# RF_AMP.net
KiCad netlist of a schematic drawn in Altium Designer
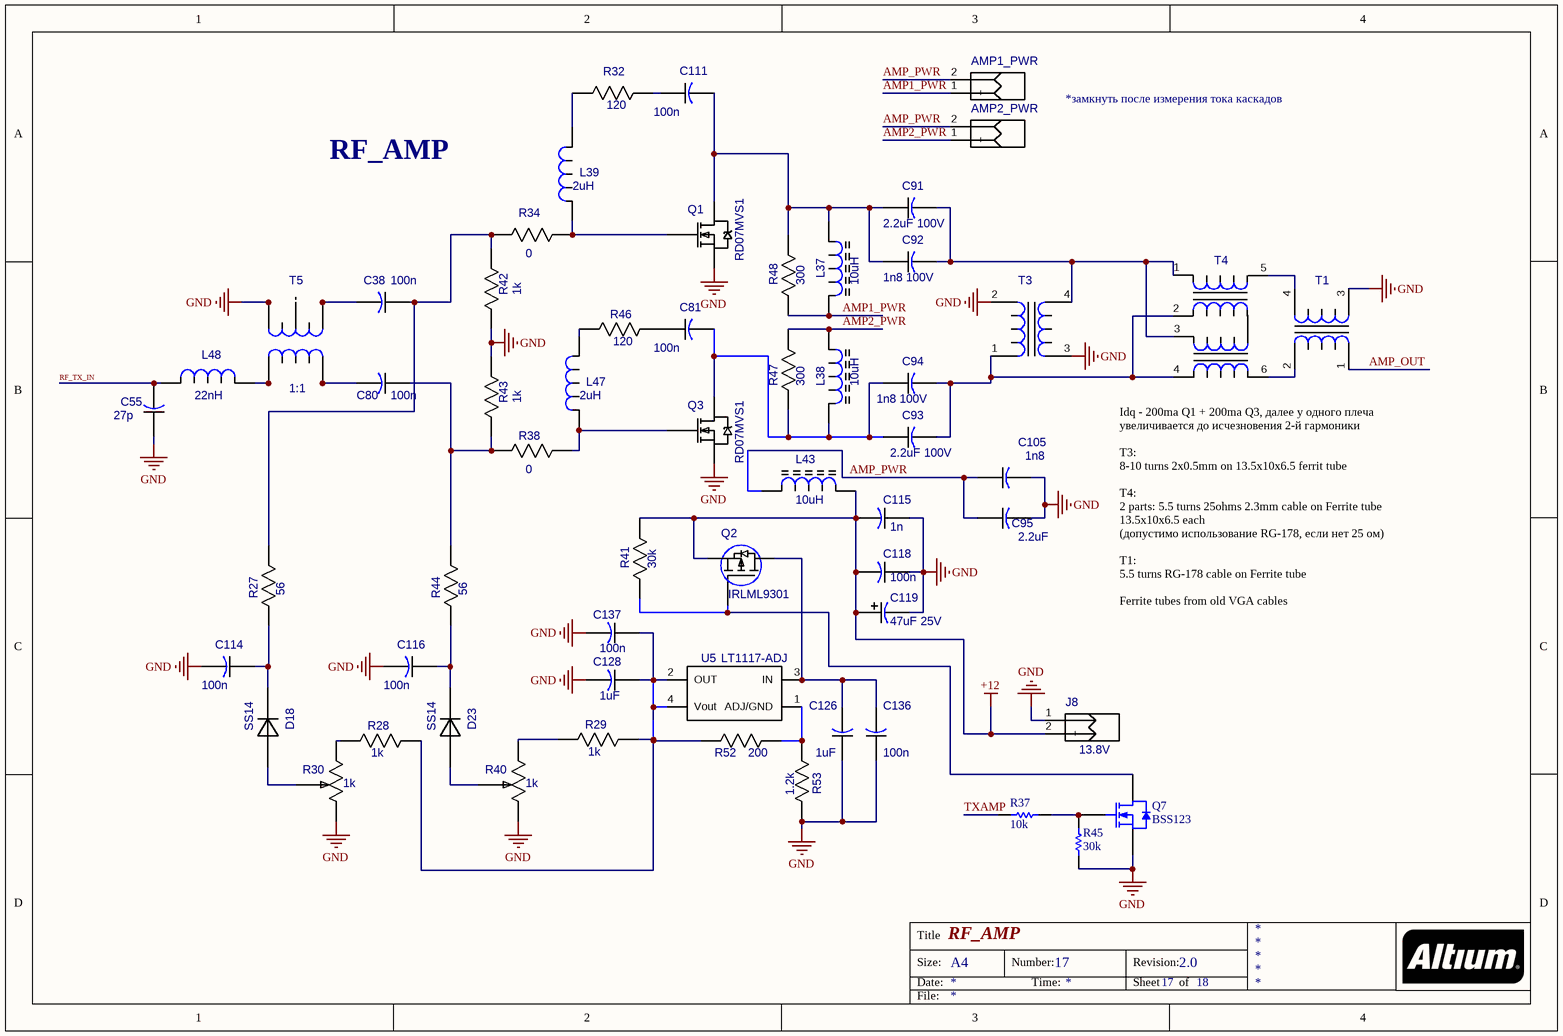
[diagram p0: RF_AMP.SchDoc]

(export (version "E")
  (design (tool "Eeschema 10.0.6"))
  (components
    (comp (ref "AMP1_PWR")
      (value "51022-0200")
      (footprint "51022-0200")
      (libsource (lib "*") (part "51022-0200"))
    )
    (comp (ref "AMP2_PWR")
      (value "51022-0200")
      (footprint "51022-0200")
      (libsource (lib "*") (part "51022-0200"))
    )
    (comp (ref "C38")
      (value "100n")
      (footprint "CAP_0805")
      (description "CAP_0805")
      (libsource (lib "*") (part "CAP_0805"))
    )
    (comp (ref "C55")
      (value "27p")
      (footprint "CAP_0805")
      (description "CAP_0805")
      (libsource (lib "*") (part "CAP_0805"))
    )
    (comp (ref "C80")
      (value "100n")
      (footprint "CAP_0805")
      (description "CAP_0805")
      (libsource (lib "*") (part "CAP_0805"))
    )
    (comp (ref "C81")
      (value "100n")
      (footprint "CAP_1206")
      (description "CAP_1206")
      (libsource (lib "*") (part "CAP_1206"))
    )
    (comp (ref "C91")
      (value "2.2uF 100V")
      (footprint "CAP_1206")
      (description "CAP_1206")
      (libsource (lib "*") (part "CAP_1206"))
    )
    (comp (ref "C92")
      (value "1n8 100V")
      (footprint "CAP_1206")
      (description "CAP_1206")
      (libsource (lib "*") (part "CAP_1206"))
    )
    (comp (ref "C93")
      (value "2.2uF 100V")
      (footprint "CAP_1206")
      (description "CAP_1206")
      (libsource (lib "*") (part "CAP_1206"))
    )
    (comp (ref "C94")
      (value "1n8 100V")
      (footprint "CAP_1206")
      (description "CAP_1206")
      (libsource (lib "*") (part "CAP_1206"))
    )
    (comp (ref "C95")
      (value "2.2uF")
      (footprint "CAP_1206")
      (description "CAP_1206")
      (libsource (lib "*") (part "CAP_1206"))
    )
    (comp (ref "C105")
      (value "1n8")
      (footprint "CAP_1206")
      (description "CAP_1206")
      (libsource (lib "*") (part "CAP_1206"))
    )
    (comp (ref "C111")
      (value "100n")
      (footprint "CAP_1206")
      (description "CAP_1206")
      (libsource (lib "*") (part "CAP_1206"))
    )
    (comp (ref "C114")
      (value "100n")
      (footprint "CAP_0805")
      (description "CAP_0805")
      (libsource (lib "*") (part "CAP_0805"))
    )
    (comp (ref "C115")
      (value "1n")
      (footprint "CAP_0805")
      (description "CAP_0805")
      (libsource (lib "*") (part "CAP_0805"))
    )
    (comp (ref "C116")
      (value "100n")
      (footprint "CAP_0805")
      (description "CAP_0805")
      (libsource (lib "*") (part "CAP_0805"))
    )
    (comp (ref "C118")
      (value "100n")
      (footprint "CAP_0805")
      (description "CAP_0805")
      (libsource (lib "*") (part "CAP_0805"))
    )
    (comp (ref "C119")
      (value "47uF 25V")
      (footprint "CAPAE_6.6x6.6h5.4")
      (description "CAPAE_6.6x6.6h5.4")
      (libsource (lib "*") (part "CAPAE_6.6x6.6h5.4"))
    )
    (comp (ref "C126")
      (value "1uF")
      (footprint "CAP_0805")
      (description "CAP_0805")
      (libsource (lib "*") (part "CAP_0805"))
    )
    (comp (ref "C128")
      (value "1uF")
      (footprint "CAP_0805")
      (description "CAP_0805")
      (libsource (lib "*") (part "CAP_0805"))
    )
    (comp (ref "C136")
      (value "100n")
      (footprint "CAP_0805")
      (description "CAP_0805")
      (libsource (lib "*") (part "CAP_0805"))
    )
    (comp (ref "C137")
      (value "100n")
      (footprint "CAP_0805")
      (description "CAP_0805")
      (libsource (lib "*") (part "CAP_0805"))
    )
    (comp (ref "D18") (value "SS14") (footprint "SS14") (libsource (lib "*") (part "SS14")))
    (comp (ref "D23") (value "SS14") (footprint "SS14") (libsource (lib "*") (part "SS14")))
    (comp (ref "J8")
      (value "13.8V")
      (footprint "1986717-2")
      (description "JX2")
      (libsource (lib "*") (part "1986717-2"))
    )
    (comp (ref "L37")
      (value "10uH")
      (footprint "IND_FERRITE_CORE")
      (description "Inductor")
      (libsource (lib "*") (part "IND_FERRITE_CORE"))
    )
    (comp (ref "L38")
      (value "10uH")
      (footprint "IND_FERRITE_CORE")
      (description "Inductor")
      (libsource (lib "*") (part "IND_FERRITE_CORE"))
    )
    (comp (ref "L39")
      (value "2uH")
      (footprint "IND_0805")
      (description "IND_0805")
      (libsource (lib "*") (part "IND_0805"))
    )
    (comp (ref "L43")
      (value "10uH")
      (footprint "IND_FERRITE_CORE")
      (description "Inductor")
      (libsource (lib "*") (part "IND_FERRITE_CORE"))
    )
    (comp (ref "L47")
      (value "2uH")
      (footprint "IND_0805")
      (description "IND_0805")
      (libsource (lib "*") (part "IND_0805"))
    )
    (comp (ref "L48")
      (value "22nH")
      (footprint "IND_0805")
      (description "IND_0805")
      (libsource (lib "*") (part "IND_0805"))
    )
    (comp (ref "Q1") (value "RD07MVS1") (footprint "RD07MVS1") (libsource (lib "*") (part "RD07MVS1")))
    (comp (ref "Q2")
      (value "IRLML9301")
      (footprint "SOT23")
      (description "MOSFET")
      (libsource (lib "*") (part "MOSFET_ENH_PD"))
    )
    (comp (ref "Q3") (value "RD07MVS1") (footprint "RD07MVS1") (libsource (lib "*") (part "RD07MVS1")))
    (comp (ref "Q7")
      (value "BSS123")
      (footprint "FAIR-SOT23-3_V")
      (fields (field (name "MANUFACTURER") "Fairchild"))
      (libsource (lib "Altium Content Vault") (part "NEMOS-GSD-3"))
    )
    (comp (ref "R27")
      (value "56")
      (footprint "RES_0805")
      (description "RES_0805")
      (libsource (lib "*") (part "RES_0805"))
    )
    (comp (ref "R28")
      (value "1k")
      (footprint "RES_0805")
      (description "RES_0805")
      (libsource (lib "*") (part "RES_0805"))
    )
    (comp (ref "R29")
      (value "1k")
      (footprint "RES_0805")
      (description "RES_0805")
      (libsource (lib "*") (part "RES_0805"))
    )
    (comp (ref "R30")
      (value "1k")
      (footprint "306J")
      (description "306J")
      (fields (field (name "Comment") "ADJ-1k"))
      (libsource (lib "*") (part "306J"))
    )
    (comp (ref "R32")
      (value "120")
      (footprint "RES_0805")
      (description "RES_0805")
      (libsource (lib "*") (part "RES_0805"))
    )
    (comp (ref "R34")
      (value "0")
      (footprint "RES_1206")
      (description "RES_1206")
      (libsource (lib "*") (part "RES_1206"))
    )
    (comp (ref "R37")
      (value "10k")
      (footprint "RESC2013X60X40NL20T25")
      (description "RES_0805")
      (fields (field (name "MANUFACTURER") "Panasonic") (field (name "PART NUMBER") "ERA-6AEB303V"))
      (libsource (lib "Altium Content Vault") (part "RES"))
    )
    (comp (ref "R38")
      (value "0")
      (footprint "RES_1206")
      (description "RES_1206")
      (libsource (lib "*") (part "RES_1206"))
    )
    (comp (ref "R40")
      (value "1k")
      (footprint "306J")
      (description "306J")
      (fields (field (name "Comment") "ADJ-1k"))
      (libsource (lib "*") (part "306J"))
    )
    (comp (ref "R41")
      (value "30k")
      (footprint "RES_0805")
      (description "RES_0805")
      (libsource (lib "*") (part "RES_0805"))
    )
    (comp (ref "R42")
      (value "1k")
      (footprint "RES_0805")
      (description "RES_0805")
      (libsource (lib "*") (part "RES_0805"))
    )
    (comp (ref "R43")
      (value "1k")
      (footprint "RES_0805")
      (description "RES_0805")
      (libsource (lib "*") (part "RES_0805"))
    )
    (comp (ref "R44")
      (value "56")
      (footprint "RES_0805")
      (description "RES_0805")
      (libsource (lib "*") (part "RES_0805"))
    )
    (comp (ref "R45")
      (value "30k")
      (footprint "RESC2013X60X40NL20T25")
      (description "RES_0805")
      (fields (field (name "MANUFACTURER") "Panasonic") (field (name "PART NUMBER") "ERA-6AEB303V"))
      (libsource (lib "Altium Content Vault") (part "RES"))
    )
    (comp (ref "R46")
      (value "120")
      (footprint "RES_0805")
      (description "RES_0805")
      (libsource (lib "*") (part "RES_0805"))
    )
    (comp (ref "R47")
      (value "300")
      (footprint "RES_1206")
      (description "RES_1206")
      (libsource (lib "*") (part "RES_1206"))
    )
    (comp (ref "R48")
      (value "300")
      (footprint "RES_1206")
      (description "RES_1206")
      (libsource (lib "*") (part "RES_1206"))
    )
    (comp (ref "R52")
      (value "200")
      (footprint "RES_0805")
      (description "RES_0805")
      (libsource (lib "*") (part "RES_0805"))
    )
    (comp (ref "R53")
      (value "1.2k")
      (footprint "RES_0805")
      (description "RES_0805")
      (libsource (lib "*") (part "RES_0805"))
    )
    (comp (ref "T1")
      (value "8T M2000HM 10*6*5")
      (footprint "Rutrof 2")
      (description "Transformer")
      (libsource (lib "*") (part "TRANSF_ICORE"))
    )
    (comp (ref "T3")
      (value "8T M2000HM 10*6*5")
      (footprint "Rutrof")
      (description "Transformer")
      (libsource (lib "*") (part "TRANSF_ICORE"))
    )
    (comp (ref "T4")
      (value "TRANSF_OUT")
      (footprint "TRANSF_OUT")
      (libsource (lib "RF-UNIT") (part "TRANSF_OUT_2"))
    )
    (comp (ref "T5")
      (value "1:1")
      (footprint "TRANSF_ACORE2")
      (libsource (lib "RF-UNIT_1") (part "TRANSF_ACORE2"))
    )
    (comp (ref "U5")
      (value "LT1117-ADJ")
      (footprint "LT1117IST-ADJ")
      (description "LT1117IST-ADJ")
      (libsource (lib "*") (part "LT1117IST-ADJ"))
    )
  )
  (nets
    (net (code "1") (name "+12") (class "Default")
      (node (ref "C115") (pin "2") (pinfunction "2_2") (pintype "passive"))
      (node (ref "C118") (pin "2") (pinfunction "2_2") (pintype "passive"))
      (node (ref "C119") (pin "1") (pinfunction "PLUS_1") (pintype "passive"))
      (node (ref "J8") (pin "2") (pinfunction "+_2") (pintype "passive"))
      (node (ref "L43") (pin "2") (pinfunction "B_2") (pintype "passive"))
      (node (ref "Q2") (pin "2") (pinfunction "S_2") (pintype "passive"))
      (node (ref "R41") (pin "2") (pinfunction "2_2") (pintype "passive"))
    )
    (net (code "2") (name "/AMP1_PWR") (class "Default")
      (node (ref "AMP1_PWR") (pin "1") (pinfunction "+_1") (pintype "passive"))
      (node (ref "L37") (pin "2") (pinfunction "B_2") (pintype "passive"))
      (node (ref "R48") (pin "1") (pinfunction "1_1") (pintype "passive"))
    )
    (net (code "3") (name "/AMP2_PWR") (class "Default")
      (node (ref "AMP2_PWR") (pin "1") (pinfunction "+_1") (pintype "passive"))
      (node (ref "L38") (pin "1") (pinfunction "A_1") (pintype "passive"))
      (node (ref "R47") (pin "2") (pinfunction "2_2") (pintype "passive"))
    )
    (net (code "4") (name "/AMP_OUT") (class "Default")
      (node (ref "T1") (pin "1") (pinfunction "P1_1") (pintype "passive"))
    )
    (net (code "5") (name "/AMP_PWR") (class "Default")
      (node (ref "AMP1_PWR") (pin "2") (pinfunction "-_2") (pintype "passive"))
      (node (ref "AMP2_PWR") (pin "2") (pinfunction "-_2") (pintype "passive"))
      (node (ref "C105") (pin "1") (pinfunction "1_1") (pintype "passive"))
      (node (ref "C95") (pin "1") (pinfunction "1_1") (pintype "passive"))
      (node (ref "L43") (pin "1") (pinfunction "A_1") (pintype "passive"))
    )
    (net (code "6") (name "/RF_TX_IN") (class "Default")
      (node (ref "C55") (pin "2") (pinfunction "2_2") (pintype "passive"))
      (node (ref "L48") (pin "1") (pinfunction "1_1") (pintype "passive"))
    )
    (net (code "7") (name "/TXAMP") (class "Default")
      (node (ref "R37") (pin "2") (pinfunction "2_2") (pintype "passive"))
    )
    (net (code "8") (name "GND") (class "Default")
      (node (ref "C105") (pin "2") (pinfunction "2_2") (pintype "passive"))
      (node (ref "C114") (pin "2") (pinfunction "2_2") (pintype "passive"))
      (node (ref "C115") (pin "1") (pinfunction "1_1") (pintype "passive"))
      (node (ref "C116") (pin "2") (pinfunction "2_2") (pintype "passive"))
      (node (ref "C118") (pin "1") (pinfunction "1_1") (pintype "passive"))
      (node (ref "C119") (pin "2") (pinfunction "MINUS_2") (pintype "passive"))
      (node (ref "C126") (pin "1") (pinfunction "1_1") (pintype "passive"))
      (node (ref "C128") (pin "2") (pinfunction "2_2") (pintype "passive"))
      (node (ref "C136") (pin "1") (pinfunction "1_1") (pintype "passive"))
      (node (ref "C137") (pin "2") (pinfunction "2_2") (pintype "passive"))
      (node (ref "C55") (pin "1") (pinfunction "1_1") (pintype "passive"))
      (node (ref "C95") (pin "2") (pinfunction "2_2") (pintype "passive"))
      (node (ref "J8") (pin "1") (pinfunction "-_1") (pintype "passive"))
      (node (ref "Q1") (pin "2") (pinfunction "S_2") (pintype "passive"))
      (node (ref "Q3") (pin "2") (pinfunction "S_2") (pintype "passive"))
      (node (ref "Q7") (pin "2") (pinfunction "S_2") (pintype "passive"))
      (node (ref "R30") (pin "1") (pinfunction "CCW_1") (pintype "passive"))
      (node (ref "R40") (pin "1") (pinfunction "CCW_1") (pintype "passive"))
      (node (ref "R42") (pin "1") (pinfunction "1_1") (pintype "passive"))
      (node (ref "R43") (pin "2") (pinfunction "2_2") (pintype "passive"))
      (node (ref "R45") (pin "1") (pinfunction "1_1") (pintype "passive"))
      (node (ref "R53") (pin "2") (pinfunction "2_2") (pintype "passive"))
      (node (ref "T1") (pin "3") (pinfunction "S1_3") (pintype "passive"))
      (node (ref "T3") (pin "2") (pinfunction "P2_2") (pintype "passive"))
      (node (ref "T3") (pin "3") (pinfunction "S1_3") (pintype "passive"))
      (node (ref "T5") (pin "3") (pinfunction "S3_3") (pintype "passive"))
      (node (ref "T5") (pin "9") (pinfunction "0_9") (pintype "passive"))
    )
    (net (code "9") (name "Net-(C38-Pad1)") (class "Default")
      (node (ref "C38") (pin "1") (pinfunction "1_1") (pintype "passive"))
      (node (ref "R27") (pin "2") (pinfunction "2_2") (pintype "passive"))
      (node (ref "R34") (pin "1") (pinfunction "1_1") (pintype "passive"))
      (node (ref "R42") (pin "2") (pinfunction "2_2") (pintype "passive"))
    )
    (net (code "10") (name "Net-(C80-Pad1)") (class "Default")
      (node (ref "C80") (pin "1") (pinfunction "1_1") (pintype "passive"))
      (node (ref "R38") (pin "1") (pinfunction "1_1") (pintype "passive"))
      (node (ref "R43") (pin "1") (pinfunction "1_1") (pintype "passive"))
      (node (ref "R44") (pin "2") (pinfunction "2_2") (pintype "passive"))
    )
    (net (code "11") (name "Net-(C81-Pad1)") (class "Default")
      (node (ref "C81") (pin "1") (pinfunction "1_1") (pintype "passive"))
      (node (ref "R46") (pin "2") (pinfunction "2_2") (pintype "passive"))
    )
    (net (code "12") (name "Net-(C111-Pad1)") (class "Default")
      (node (ref "C111") (pin "1") (pinfunction "1_1") (pintype "passive"))
      (node (ref "R32") (pin "2") (pinfunction "2_2") (pintype "passive"))
    )
    (net (code "13") (name "Net-(D18-A)") (class "Default")
      (node (ref "D18") (pin "2") (pinfunction "A_2") (pintype "passive"))
      (node (ref "R30") (pin "2") (pinfunction "W_2") (pintype "passive"))
    )
    (net (code "14") (name "Net-(D18-K)") (class "Default")
      (node (ref "C114") (pin "1") (pinfunction "1_1") (pintype "passive"))
      (node (ref "D18") (pin "1") (pinfunction "K_1") (pintype "passive"))
      (node (ref "R27") (pin "1") (pinfunction "1_1") (pintype "passive"))
    )
    (net (code "15") (name "Net-(D23-A)") (class "Default")
      (node (ref "D23") (pin "2") (pinfunction "A_2") (pintype "passive"))
      (node (ref "R40") (pin "2") (pinfunction "W_2") (pintype "passive"))
    )
    (net (code "16") (name "Net-(D23-K)") (class "Default")
      (node (ref "C116") (pin "1") (pinfunction "1_1") (pintype "passive"))
      (node (ref "D23") (pin "1") (pinfunction "K_1") (pintype "passive"))
      (node (ref "R44") (pin "1") (pinfunction "1_1") (pintype "passive"))
    )
    (net (code "17") (name "Net-(L37-A)") (class "Default")
      (node (ref "C111") (pin "2") (pinfunction "2_2") (pintype "passive"))
      (node (ref "C91") (pin "1") (pinfunction "1_1") (pintype "passive"))
      (node (ref "C92") (pin "1") (pinfunction "1_1") (pintype "passive"))
      (node (ref "L37") (pin "1") (pinfunction "A_1") (pintype "passive"))
      (node (ref "Q1") (pin "1") (pinfunction "D_1") (pintype "passive"))
      (node (ref "R48") (pin "2") (pinfunction "2_2") (pintype "passive"))
    )
    (net (code "18") (name "Net-(L38-B)") (class "Default")
      (node (ref "C81") (pin "2") (pinfunction "2_2") (pintype "passive"))
      (node (ref "C93") (pin "1") (pinfunction "1_1") (pintype "passive"))
      (node (ref "C94") (pin "1") (pinfunction "1_1") (pintype "passive"))
      (node (ref "L38") (pin "2") (pinfunction "B_2") (pintype "passive"))
      (node (ref "Q3") (pin "1") (pinfunction "D_1") (pintype "passive"))
      (node (ref "R47") (pin "1") (pinfunction "1_1") (pintype "passive"))
    )
    (net (code "19") (name "Net-(L39-Pad2)") (class "Default")
      (node (ref "L39") (pin "2") (pinfunction "2_2") (pintype "passive"))
      (node (ref "R32") (pin "1") (pinfunction "1_1") (pintype "passive"))
    )
    (net (code "20") (name "Net-(L47-Pad2)") (class "Default")
      (node (ref "L47") (pin "2") (pinfunction "2_2") (pintype "passive"))
      (node (ref "R46") (pin "1") (pinfunction "1_1") (pintype "passive"))
    )
    (net (code "21") (name "Net-(Q1-G)") (class "Default")
      (node (ref "L39") (pin "1") (pinfunction "1_1") (pintype "passive"))
      (node (ref "Q1") (pin "3") (pinfunction "G_3") (pintype "passive"))
      (node (ref "R34") (pin "2") (pinfunction "2_2") (pintype "passive"))
    )
    (net (code "22") (name "Net-(Q2-D)") (class "Default")
      (node (ref "C126") (pin "2") (pinfunction "2_2") (pintype "passive"))
      (node (ref "C136") (pin "2") (pinfunction "2_2") (pintype "passive"))
      (node (ref "Q2") (pin "3") (pinfunction "D_3") (pintype "passive"))
      (node (ref "U5") (pin "3") (pinfunction "IN_3") (pintype "passive"))
    )
    (net (code "23") (name "Net-(Q2-G)") (class "Default")
      (node (ref "Q2") (pin "1") (pinfunction "G_1") (pintype "passive"))
      (node (ref "Q7") (pin "3") (pinfunction "D_3") (pintype "passive"))
      (node (ref "R41") (pin "1") (pinfunction "1_1") (pintype "passive"))
    )
    (net (code "24") (name "Net-(Q3-G)") (class "Default")
      (node (ref "L47") (pin "1") (pinfunction "1_1") (pintype "passive"))
      (node (ref "Q3") (pin "3") (pinfunction "G_3") (pintype "passive"))
      (node (ref "R38") (pin "2") (pinfunction "2_2") (pintype "passive"))
    )
    (net (code "25") (name "Net-(Q7-G)") (class "Default")
      (node (ref "Q7") (pin "1") (pinfunction "G_1") (pintype "passive"))
      (node (ref "R37") (pin "1") (pinfunction "1_1") (pintype "passive"))
      (node (ref "R45") (pin "2") (pinfunction "2_2") (pintype "passive"))
    )
    (net (code "26") (name "Net-(R30-CW)") (class "Default")
      (node (ref "R28") (pin "1") (pinfunction "1_1") (pintype "passive"))
      (node (ref "R30") (pin "3") (pinfunction "CW_3") (pintype "passive"))
    )
    (net (code "27") (name "Net-(R40-CW)") (class "Default")
      (node (ref "R29") (pin "1") (pinfunction "1_1") (pintype "passive"))
      (node (ref "R40") (pin "3") (pinfunction "CW_3") (pintype "passive"))
    )
    (net (code "28") (name "Net-(T1-P2)") (class "Default")
      (node (ref "T1") (pin "2") (pinfunction "P2_2") (pintype "passive"))
      (node (ref "T4") (pin "6") (pinfunction "OUT2_6") (pintype "passive"))
    )
    (net (code "29") (name "Net-(T1-S2)") (class "Default")
      (node (ref "T1") (pin "4") (pinfunction "S2_4") (pintype "passive"))
      (node (ref "T4") (pin "5") (pinfunction "OUT1_5") (pintype "passive"))
    )
    (net (code "30") (name "Net-(T3-P1)") (class "Default")
      (node (ref "C93") (pin "2") (pinfunction "2_2") (pintype "passive"))
      (node (ref "C94") (pin "2") (pinfunction "2_2") (pintype "passive"))
      (node (ref "T3") (pin "1") (pinfunction "P1_1") (pintype "passive"))
      (node (ref "T4") (pin "2") (pinfunction "T1N_2") (pintype "passive"))
      (node (ref "T4") (pin "4") (pinfunction "T2P_4") (pintype "passive"))
    )
    (net (code "31") (name "Net-(T3-S2)") (class "Default")
      (node (ref "C91") (pin "2") (pinfunction "2_2") (pintype "passive"))
      (node (ref "C92") (pin "2") (pinfunction "2_2") (pintype "passive"))
      (node (ref "T3") (pin "4") (pinfunction "S2_4") (pintype "passive"))
      (node (ref "T4") (pin "1") (pinfunction "T1P_1") (pintype "passive"))
      (node (ref "T4") (pin "3") (pinfunction "T2N_3") (pintype "passive"))
    )
    (net (code "32") (name "Net-(T5-P1)") (class "Default")
      (node (ref "C80") (pin "2") (pinfunction "2_2") (pintype "passive"))
      (node (ref "T5") (pin "10") (pinfunction "0_10") (pintype "passive"))
      (node (ref "T5") (pin "6") (pinfunction "P1_6") (pintype "passive"))
    )
    (net (code "33") (name "Net-(T5-P2)") (class "Default")
      (node (ref "L48") (pin "2") (pinfunction "2_2") (pintype "passive"))
      (node (ref "T5") (pin "11") (pinfunction "0_11") (pintype "passive"))
      (node (ref "T5") (pin "4") (pinfunction "P2_4") (pintype "passive"))
    )
    (net (code "34") (name "Net-(T5-S1)") (class "Default")
      (node (ref "C38") (pin "2") (pinfunction "2_2") (pintype "passive"))
      (node (ref "T5") (pin "1") (pinfunction "S1_1") (pintype "passive"))
      (node (ref "T5") (pin "7") (pinfunction "0_7") (pintype "passive"))
    )
    (net (code "35") (name "Net-(U5-ADJ{slash}GND)") (class "Default")
      (node (ref "R52") (pin "2") (pinfunction "2_2") (pintype "passive"))
      (node (ref "R53") (pin "1") (pinfunction "1_1") (pintype "passive"))
      (node (ref "U5") (pin "1") (pinfunction "ADJ/GND_1") (pintype "passive"))
    )
    (net (code "36") (name "Net-(U5-OUT)") (class "Default")
      (node (ref "C128") (pin "1") (pinfunction "1_1") (pintype "passive"))
      (node (ref "C137") (pin "1") (pinfunction "1_1") (pintype "passive"))
      (node (ref "R28") (pin "2") (pinfunction "2_2") (pintype "passive"))
      (node (ref "R29") (pin "2") (pinfunction "2_2") (pintype "passive"))
      (node (ref "R52") (pin "1") (pinfunction "1_1") (pintype "passive"))
      (node (ref "U5") (pin "2") (pinfunction "OUT_2") (pintype "passive"))
      (node (ref "U5") (pin "4") (pinfunction "Vout_4") (pintype "passive"))
    )
    (net (code "37") (name "unconnected-(T5-S2-Pad2)") (class "Default")
      (node (ref "T5") (pin "2") (pinfunction "S2_2") (pintype "passive"))
    )
    (net (code "38") (name "unconnected-(T5-S2-Pad8)") (class "Default")
      (node (ref "T5") (pin "8") (pinfunction "S2_8") (pintype "passive"))
    )
  )
)
